# Capteur_IR.net
KiCad netlist of a schematic drawn in Altium Designer
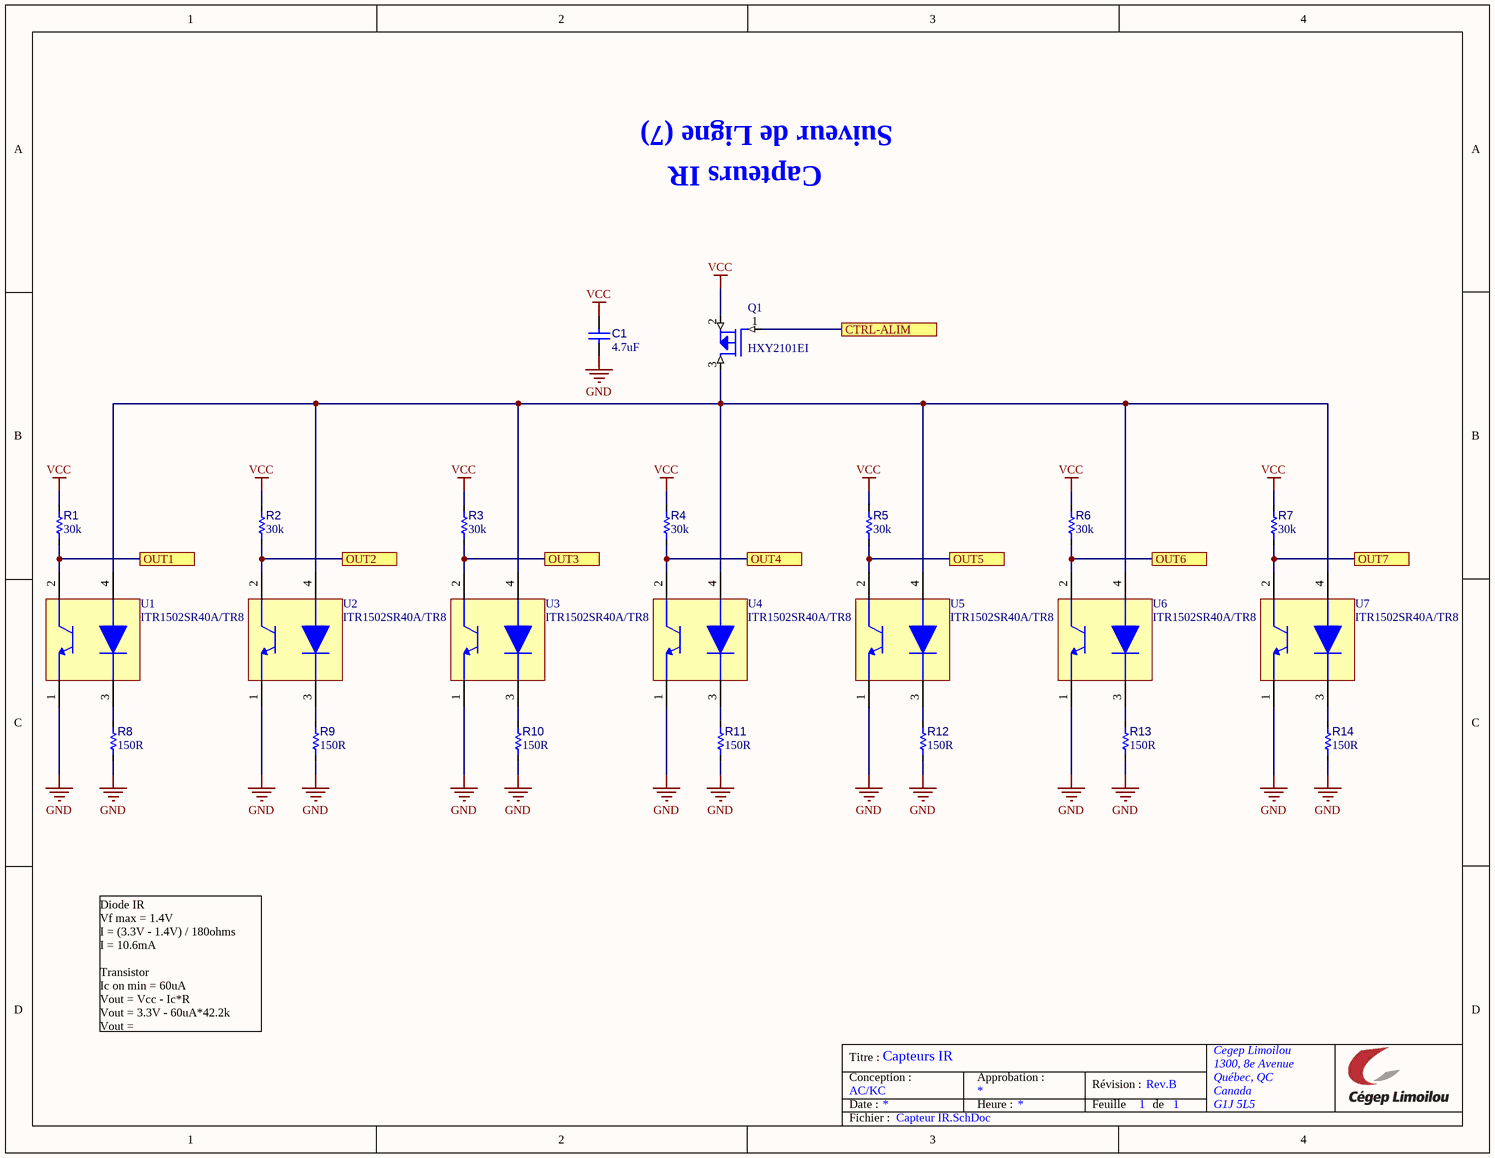
[diagram p0: Capteur IR.SchDoc]

(export (version "E")
  (design (tool "Eeschema 10.0.6"))
  (components
    (comp (ref "C1")
      (value "4.7uF")
      (footprint "C_2012[0805]")
      (description "Capacitor type 1")
      (fields (field (name "TOLERANCE") "10%") (field (name "Comment") "CAP CER 4.7uF 25V X7R 0805"))
      (libsource (lib "TEP_243-Altium_DBLib") (part "capacitor"))
    )
    (comp (ref "Q1")
      (value "HXY2101EI")
      (footprint "SOT-323")
      (description "MOSFET P-CH 20V 1.8A SOT-323")
      (libsource (lib "TEP-AltiumLib-Discretes") (part "Q_PMOS-20V-1.8A"))
    )
    (comp (ref "R1")
      (value "30k")
      (footprint "R_1608[0603]")
      (description "Resistor type 1")
      (fields (field (name "TOLERANCE") "1%") (field (name "Comment") "Res 30k 1% 0603"))
      (libsource (lib "TEP_243-Altium_DBLib") (part "resistor"))
    )
    (comp (ref "R2")
      (value "30k")
      (footprint "R_1608[0603]")
      (description "Resistor type 1")
      (fields (field (name "TOLERANCE") "1%") (field (name "Comment") "Res 30k 1% 0603"))
      (libsource (lib "TEP_243-Altium_DBLib") (part "resistor"))
    )
    (comp (ref "R3")
      (value "30k")
      (footprint "R_1608[0603]")
      (description "Resistor type 1")
      (fields (field (name "TOLERANCE") "1%") (field (name "Comment") "Res 30k 1% 0603"))
      (libsource (lib "TEP_243-Altium_DBLib") (part "resistor"))
    )
    (comp (ref "R4")
      (value "30k")
      (footprint "R_1608[0603]")
      (description "Resistor type 1")
      (fields (field (name "TOLERANCE") "1%") (field (name "Comment") "Res 30k 1% 0603"))
      (libsource (lib "TEP_243-Altium_DBLib") (part "resistor"))
    )
    (comp (ref "R5")
      (value "30k")
      (footprint "R_1608[0603]")
      (description "Resistor type 1")
      (fields (field (name "TOLERANCE") "1%") (field (name "Comment") "Res 30k 1% 0603"))
      (libsource (lib "TEP_243-Altium_DBLib") (part "resistor"))
    )
    (comp (ref "R6")
      (value "30k")
      (footprint "R_1608[0603]")
      (description "Resistor type 1")
      (fields (field (name "TOLERANCE") "1%") (field (name "Comment") "Res 30k 1% 0603"))
      (libsource (lib "TEP_243-Altium_DBLib") (part "resistor"))
    )
    (comp (ref "R7")
      (value "30k")
      (footprint "R_1608[0603]")
      (description "Resistor type 1")
      (fields (field (name "TOLERANCE") "1%") (field (name "Comment") "Res 30k 1% 0603"))
      (libsource (lib "TEP_243-Altium_DBLib") (part "resistor"))
    )
    (comp (ref "R8")
      (value "150R")
      (footprint "R_3216[1206]")
      (description "Resistor type 1")
      (fields (field (name "TOLERANCE") "5%") (field (name "Comment") "Res 150R 5% 1206"))
      (libsource (lib "TEP_243-Altium_DBLib") (part "resistor"))
    )
    (comp (ref "R9")
      (value "150R")
      (footprint "R_3216[1206]")
      (description "Resistor type 1")
      (fields (field (name "TOLERANCE") "5%") (field (name "Comment") "Res 150R 5% 1206"))
      (libsource (lib "TEP_243-Altium_DBLib") (part "resistor"))
    )
    (comp (ref "R10")
      (value "150R")
      (footprint "R_3216[1206]")
      (description "Resistor type 1")
      (fields (field (name "TOLERANCE") "5%") (field (name "Comment") "Res 150R 5% 1206"))
      (libsource (lib "TEP_243-Altium_DBLib") (part "resistor"))
    )
    (comp (ref "R11")
      (value "150R")
      (footprint "R_3216[1206]")
      (description "Resistor type 1")
      (fields (field (name "TOLERANCE") "5%") (field (name "Comment") "Res 150R 5% 1206"))
      (libsource (lib "TEP_243-Altium_DBLib") (part "resistor"))
    )
    (comp (ref "R12")
      (value "150R")
      (footprint "R_3216[1206]")
      (description "Resistor type 1")
      (fields (field (name "TOLERANCE") "5%") (field (name "Comment") "Res 150R 5% 1206"))
      (libsource (lib "TEP_243-Altium_DBLib") (part "resistor"))
    )
    (comp (ref "R13")
      (value "150R")
      (footprint "R_3216[1206]")
      (description "Resistor type 1")
      (fields (field (name "TOLERANCE") "5%") (field (name "Comment") "Res 150R 5% 1206"))
      (libsource (lib "TEP_243-Altium_DBLib") (part "resistor"))
    )
    (comp (ref "R14")
      (value "150R")
      (footprint "R_3216[1206]")
      (description "Resistor type 1")
      (fields (field (name "TOLERANCE") "5%") (field (name "Comment") "Res 150R 5% 1206"))
      (libsource (lib "TEP_243-Altium_DBLib") (part "resistor"))
    )
    (comp (ref "U1")
      (value "ITR1502SR40A/TR8")
      (footprint "GP2S700HCP")
      (description "PHOTOINTERRUPTER REFLECTIVE 3MM SMD")
      (libsource (lib "TEP-AltiumLib-ICs") (part "U_ITR1502SR40A/TR8"))
    )
    (comp (ref "U2")
      (value "ITR1502SR40A/TR8")
      (footprint "GP2S700HCP")
      (description "PHOTOINTERRUPTER REFLECTIVE 3MM SMD")
      (libsource (lib "TEP-AltiumLib-ICs") (part "U_ITR1502SR40A/TR8"))
    )
    (comp (ref "U3")
      (value "ITR1502SR40A/TR8")
      (footprint "GP2S700HCP")
      (description "PHOTOINTERRUPTER REFLECTIVE 3MM SMD")
      (libsource (lib "TEP-AltiumLib-ICs") (part "U_ITR1502SR40A/TR8"))
    )
    (comp (ref "U4")
      (value "ITR1502SR40A/TR8")
      (footprint "GP2S700HCP")
      (description "PHOTOINTERRUPTER REFLECTIVE 3MM SMD")
      (libsource (lib "TEP-AltiumLib-ICs") (part "U_ITR1502SR40A/TR8"))
    )
    (comp (ref "U5")
      (value "ITR1502SR40A/TR8")
      (footprint "GP2S700HCP")
      (description "PHOTOINTERRUPTER REFLECTIVE 3MM SMD")
      (libsource (lib "TEP-AltiumLib-ICs") (part "U_ITR1502SR40A/TR8"))
    )
    (comp (ref "U6")
      (value "ITR1502SR40A/TR8")
      (footprint "GP2S700HCP")
      (description "PHOTOINTERRUPTER REFLECTIVE 3MM SMD")
      (libsource (lib "TEP-AltiumLib-ICs") (part "U_ITR1502SR40A/TR8"))
    )
    (comp (ref "U7")
      (value "ITR1502SR40A/TR8")
      (footprint "GP2S700HCP")
      (description "PHOTOINTERRUPTER REFLECTIVE 3MM SMD")
      (libsource (lib "TEP-AltiumLib-ICs") (part "U_ITR1502SR40A/TR8"))
    )
  )
  (nets
    (net (code "1") (name "/CTRL-ALIM") (class "Default")
      (node (ref "Q1") (pin "1") (pinfunction "GATE_1") (pintype "input"))
    )
    (net (code "2") (name "/OUT1") (class "Default")
      (node (ref "R1") (pin "1") (pinfunction "1_1") (pintype "passive"))
      (node (ref "U1") (pin "2") (pinfunction "C_2") (pintype "passive"))
    )
    (net (code "3") (name "/OUT2") (class "Default")
      (node (ref "R2") (pin "1") (pinfunction "1_1") (pintype "passive"))
      (node (ref "U2") (pin "2") (pinfunction "C_2") (pintype "passive"))
    )
    (net (code "4") (name "/OUT3") (class "Default")
      (node (ref "R3") (pin "1") (pinfunction "1_1") (pintype "passive"))
      (node (ref "U3") (pin "2") (pinfunction "C_2") (pintype "passive"))
    )
    (net (code "5") (name "/OUT4") (class "Default")
      (node (ref "R4") (pin "1") (pinfunction "1_1") (pintype "passive"))
      (node (ref "U4") (pin "2") (pinfunction "C_2") (pintype "passive"))
    )
    (net (code "6") (name "/OUT5") (class "Default")
      (node (ref "R5") (pin "1") (pinfunction "1_1") (pintype "passive"))
      (node (ref "U5") (pin "2") (pinfunction "C_2") (pintype "passive"))
    )
    (net (code "7") (name "/OUT6") (class "Default")
      (node (ref "R6") (pin "1") (pinfunction "1_1") (pintype "passive"))
      (node (ref "U6") (pin "2") (pinfunction "C_2") (pintype "passive"))
    )
    (net (code "8") (name "/OUT7") (class "Default")
      (node (ref "R7") (pin "1") (pinfunction "1_1") (pintype "passive"))
      (node (ref "U7") (pin "2") (pinfunction "C_2") (pintype "passive"))
    )
    (net (code "9") (name "GND") (class "Default")
      (node (ref "C1") (pin "1") (pinfunction "1_1") (pintype "passive"))
      (node (ref "R10") (pin "1") (pinfunction "1_1") (pintype "passive"))
      (node (ref "R11") (pin "1") (pinfunction "1_1") (pintype "passive"))
      (node (ref "R12") (pin "1") (pinfunction "1_1") (pintype "passive"))
      (node (ref "R13") (pin "1") (pinfunction "1_1") (pintype "passive"))
      (node (ref "R14") (pin "1") (pinfunction "1_1") (pintype "passive"))
      (node (ref "R8") (pin "1") (pinfunction "1_1") (pintype "passive"))
      (node (ref "R9") (pin "1") (pinfunction "1_1") (pintype "passive"))
      (node (ref "U1") (pin "1") (pinfunction "E_1") (pintype "passive"))
      (node (ref "U2") (pin "1") (pinfunction "E_1") (pintype "passive"))
      (node (ref "U3") (pin "1") (pinfunction "E_1") (pintype "passive"))
      (node (ref "U4") (pin "1") (pinfunction "E_1") (pintype "passive"))
      (node (ref "U5") (pin "1") (pinfunction "E_1") (pintype "passive"))
      (node (ref "U6") (pin "1") (pinfunction "E_1") (pintype "passive"))
      (node (ref "U7") (pin "1") (pinfunction "E_1") (pintype "passive"))
    )
    (net (code "10") (name "Net-(Q1-DRAIN)") (class "Default")
      (node (ref "Q1") (pin "3") (pinfunction "DRAIN_3") (pintype "input"))
      (node (ref "U1") (pin "4") (pinfunction "A_4") (pintype "passive"))
      (node (ref "U2") (pin "4") (pinfunction "A_4") (pintype "passive"))
      (node (ref "U3") (pin "4") (pinfunction "A_4") (pintype "passive"))
      (node (ref "U4") (pin "4") (pinfunction "A_4") (pintype "passive"))
      (node (ref "U5") (pin "4") (pinfunction "A_4") (pintype "passive"))
      (node (ref "U6") (pin "4") (pinfunction "A_4") (pintype "passive"))
      (node (ref "U7") (pin "4") (pinfunction "A_4") (pintype "passive"))
    )
    (net (code "11") (name "Net-(U1-K)") (class "Default")
      (node (ref "R8") (pin "2") (pinfunction "2_2") (pintype "passive"))
      (node (ref "U1") (pin "3") (pinfunction "K_3") (pintype "passive"))
    )
    (net (code "12") (name "Net-(U2-K)") (class "Default")
      (node (ref "R9") (pin "2") (pinfunction "2_2") (pintype "passive"))
      (node (ref "U2") (pin "3") (pinfunction "K_3") (pintype "passive"))
    )
    (net (code "13") (name "Net-(U3-K)") (class "Default")
      (node (ref "R10") (pin "2") (pinfunction "2_2") (pintype "passive"))
      (node (ref "U3") (pin "3") (pinfunction "K_3") (pintype "passive"))
    )
    (net (code "14") (name "Net-(U4-K)") (class "Default")
      (node (ref "R11") (pin "2") (pinfunction "2_2") (pintype "passive"))
      (node (ref "U4") (pin "3") (pinfunction "K_3") (pintype "passive"))
    )
    (net (code "15") (name "Net-(U5-K)") (class "Default")
      (node (ref "R12") (pin "2") (pinfunction "2_2") (pintype "passive"))
      (node (ref "U5") (pin "3") (pinfunction "K_3") (pintype "passive"))
    )
    (net (code "16") (name "Net-(U6-K)") (class "Default")
      (node (ref "R13") (pin "2") (pinfunction "2_2") (pintype "passive"))
      (node (ref "U6") (pin "3") (pinfunction "K_3") (pintype "passive"))
    )
    (net (code "17") (name "Net-(U7-K)") (class "Default")
      (node (ref "R14") (pin "2") (pinfunction "2_2") (pintype "passive"))
      (node (ref "U7") (pin "3") (pinfunction "K_3") (pintype "passive"))
    )
    (net (code "18") (name "VCC") (class "Default")
      (node (ref "C1") (pin "2") (pinfunction "2_2") (pintype "passive"))
      (node (ref "Q1") (pin "2") (pinfunction "SOURCE_2") (pintype "input"))
      (node (ref "R1") (pin "2") (pinfunction "2_2") (pintype "passive"))
      (node (ref "R2") (pin "2") (pinfunction "2_2") (pintype "passive"))
      (node (ref "R3") (pin "2") (pinfunction "2_2") (pintype "passive"))
      (node (ref "R4") (pin "2") (pinfunction "2_2") (pintype "passive"))
      (node (ref "R5") (pin "2") (pinfunction "2_2") (pintype "passive"))
      (node (ref "R6") (pin "2") (pinfunction "2_2") (pintype "passive"))
      (node (ref "R7") (pin "2") (pinfunction "2_2") (pintype "passive"))
    )
  )
)
